# DSO_Control.net
KiCad netlist of a schematic drawn in Altium Designer
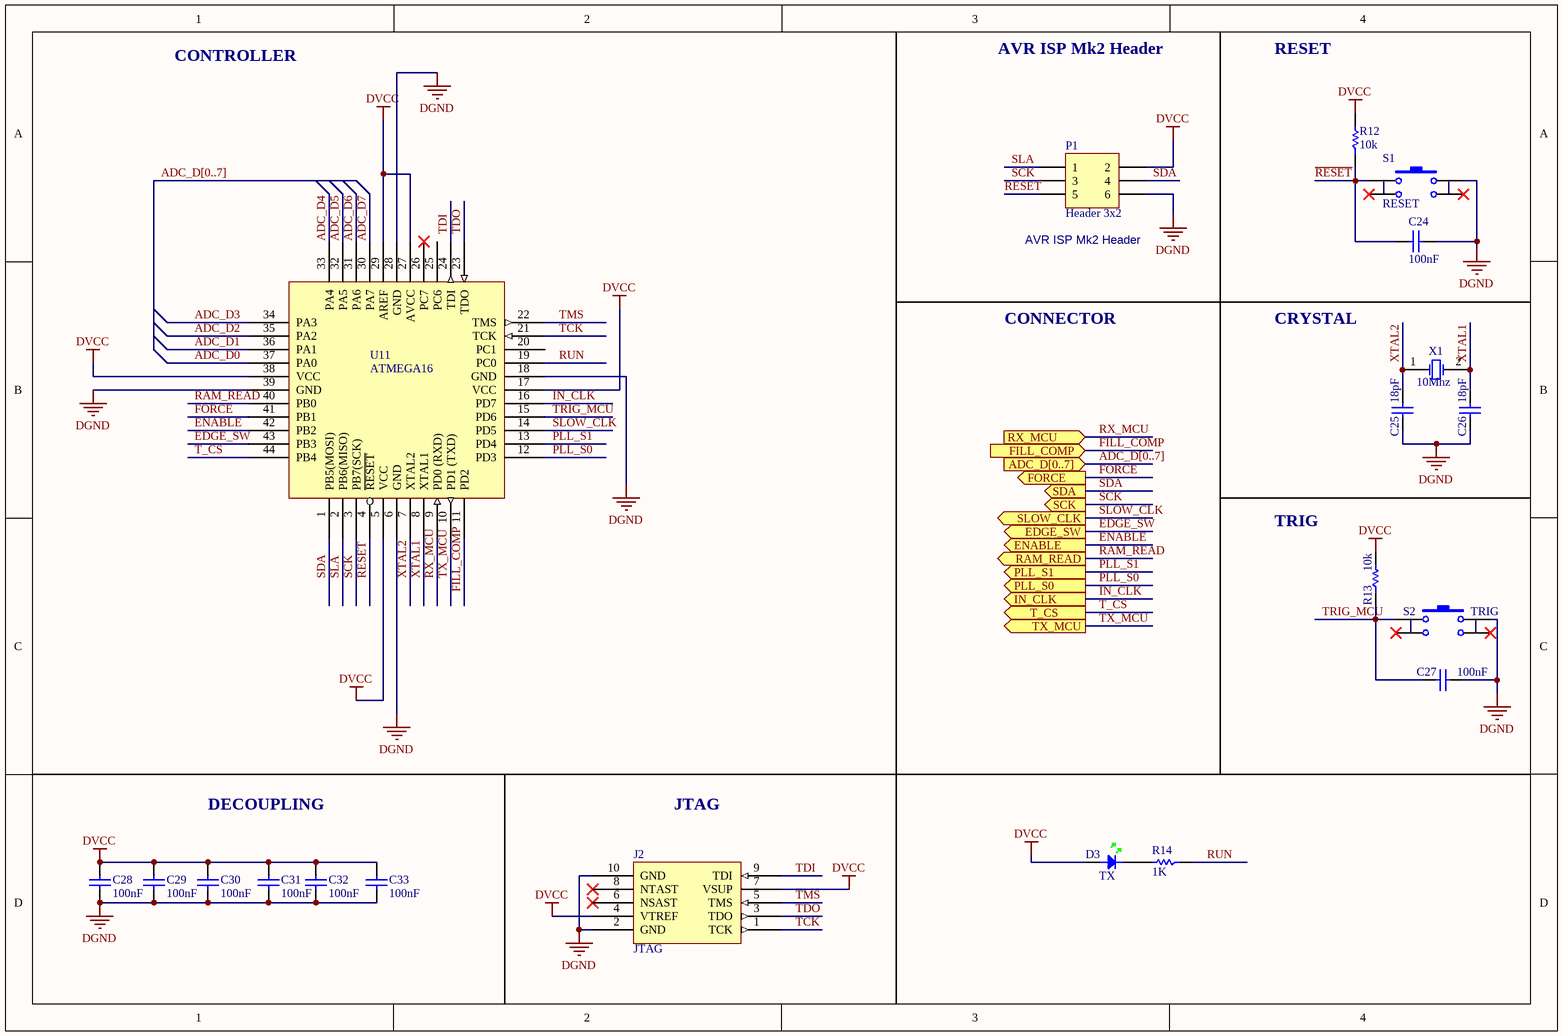
[diagram p0: DSO_Control.SchDoc]

(export (version "E")
  (design (tool "Eeschema 10.0.6"))
  (components
    (comp (ref "C24")
      (value "100nF")
      (footprint "0805C")
      (description "Capacitor")
      (fields (field (name "REVIEWED BY") "RM - 2018/08/05"))
      (libsource (lib "DSO") (part "C"))
    )
    (comp (ref "C25")
      (value "18pF")
      (footprint "0805C")
      (description "Capacitor")
      (fields (field (name "REVIEWED BY") "RM - 2018/08/05"))
      (libsource (lib "DSO") (part "C"))
    )
    (comp (ref "C26")
      (value "18pF")
      (footprint "0805C")
      (description "Capacitor")
      (fields (field (name "REVIEWED BY") "RM - 2018/08/05"))
      (libsource (lib "DSO") (part "C"))
    )
    (comp (ref "C27")
      (value "100nF")
      (footprint "0805C")
      (description "Capacitor")
      (fields (field (name "REVIEWED BY") "RM - 2018/08/05"))
      (libsource (lib "DSO") (part "C"))
    )
    (comp (ref "C28")
      (value "100nF")
      (footprint "0805C")
      (description "Capacitor")
      (fields (field (name "REVIEWED BY") "RM - 2018/08/05"))
      (libsource (lib "DSO") (part "C"))
    )
    (comp (ref "C29")
      (value "100nF")
      (footprint "0805C")
      (description "Capacitor")
      (fields (field (name "REVIEWED BY") "RM - 2018/08/05"))
      (libsource (lib "DSO") (part "C"))
    )
    (comp (ref "C30")
      (value "100nF")
      (footprint "0805C")
      (description "Capacitor")
      (fields (field (name "REVIEWED BY") "RM - 2018/08/05"))
      (libsource (lib "DSO") (part "C"))
    )
    (comp (ref "C31")
      (value "100nF")
      (footprint "0805C")
      (description "Capacitor")
      (fields (field (name "REVIEWED BY") "RM - 2018/08/05"))
      (libsource (lib "DSO") (part "C"))
    )
    (comp (ref "C32")
      (value "100nF")
      (footprint "0805C")
      (description "Capacitor")
      (fields (field (name "REVIEWED BY") "RM - 2018/08/05"))
      (libsource (lib "DSO") (part "C"))
    )
    (comp (ref "C33")
      (value "100nF")
      (footprint "0805C")
      (description "Capacitor")
      (fields (field (name "REVIEWED BY") "RM - 2018/08/05"))
      (libsource (lib "DSO") (part "C"))
    )
    (comp (ref "D3")
      (value "TX")
      (footprint "0805D-GREEN")
      (description "Light Emitting Diode")
      (fields (field (name "REVIEWED BY") "RM - 2018/08/05"))
      (libsource (lib "DSO") (part "LED GREEN"))
    )
    (comp (ref "J2")
      (value "JTAG")
      (footprint "BOXEDVERT10")
      (description "JTAG_CON")
      (fields (field (name "REVIEWED BY") "RM - 2018/08/05"))
      (libsource (lib "DSO") (part "JTAG_CON"))
    )
    (comp (ref "P1")
      (value "Header 3x2")
      (footprint "HDR3x2")
      (description "Header, 5-Pin")
      (fields (field (name "REVIEWED BY") "RM - 2018/08/05"))
      (libsource (lib "DSO") (part "Header 3x2"))
    )
    (comp (ref "R12")
      (value "10k")
      (footprint "0805")
      (description "Resistor")
      (fields (field (name "REVIEWED BY") "RM - 2018/08/05"))
      (libsource (lib "DSO") (part "R"))
    )
    (comp (ref "R13")
      (value "10k")
      (footprint "0805")
      (description "Resistor")
      (fields (field (name "REVIEWED BY") "RM - 2018/08/05"))
      (libsource (lib "DSO") (part "R"))
    )
    (comp (ref "R14")
      (value "1K")
      (footprint "0805")
      (description "Resistor")
      (libsource (lib "DSO") (part "R"))
    )
    (comp (ref "S1")
      (value "RESET")
      (footprint "SPST PB SWITCH SMD")
      (description "Momentary Push Button Switch 1P 1T 2pins")
      (fields (field (name "REVIEWED BY") "RM - 2018/08/05"))
      (libsource (lib "DSO") (part "SW_PB_1P1T4"))
    )
    (comp (ref "S2")
      (value "TRIG")
      (footprint "SPST PB SWITCH SMD")
      (description "Momentary Push Button Switch 1P 1T 2pins")
      (fields (field (name "REVIEWED BY") "RM - 2018/08/05"))
      (libsource (lib "DSO") (part "SW_PB_1P1T4"))
    )
    (comp (ref "U11")
      (value "ATMEGA16")
      (footprint "QFP-48")
      (description "ATMEGA16 Microcontroller")
      (fields (field (name "REVIEWED BY") "RM - 2018/08/05"))
      (libsource (lib "DSO") (part "ATMEGA16"))
    )
    (comp (ref "X1")
      (value "10Mhz")
      (footprint "XTAL_FLAT_SMD")
      (description "Crystal Oscillator")
      (fields (field (name "REVIEWED BY") "RM - 2018/08/05"))
      (libsource (lib "DSO") (part "XTAL"))
    )
  )
  (nets
    (net (code "1") (name "/ADC_D0") (class "Default")
      (node (ref "U11") (pin "37") (pinfunction "PA0_37") (pintype "passive"))
    )
    (net (code "2") (name "/ADC_D1") (class "Default")
      (node (ref "U11") (pin "36") (pinfunction "PA1_36") (pintype "passive"))
    )
    (net (code "3") (name "/ADC_D2") (class "Default")
      (node (ref "U11") (pin "35") (pinfunction "PA2_35") (pintype "passive"))
    )
    (net (code "4") (name "/ADC_D3") (class "Default")
      (node (ref "U11") (pin "34") (pinfunction "PA3_34") (pintype "passive"))
    )
    (net (code "5") (name "/ADC_D4") (class "Default")
      (node (ref "U11") (pin "33") (pinfunction "PA4_33") (pintype "passive"))
    )
    (net (code "6") (name "/ADC_D5") (class "Default")
      (node (ref "U11") (pin "32") (pinfunction "PA5_32") (pintype "passive"))
    )
    (net (code "7") (name "/ADC_D6") (class "Default")
      (node (ref "U11") (pin "31") (pinfunction "PA6_31") (pintype "passive"))
    )
    (net (code "8") (name "/ADC_D7") (class "Default")
      (node (ref "U11") (pin "30") (pinfunction "PA7_30") (pintype "passive"))
    )
    (net (code "10") (name "/EDGE_SW") (class "Default")
      (node (ref "U11") (pin "43") (pinfunction "PB3_43") (pintype "passive"))
    )
    (net (code "11") (name "/ENABLE") (class "Default")
      (node (ref "U11") (pin "42") (pinfunction "PB2_42") (pintype "passive"))
    )
    (net (code "12") (name "/FILL_COMP") (class "Default")
      (node (ref "U11") (pin "11") (pinfunction "PD2_11") (pintype "passive"))
    )
    (net (code "13") (name "/FORCE") (class "Default")
      (node (ref "U11") (pin "41") (pinfunction "PB1_41") (pintype "passive"))
    )
    (net (code "14") (name "/IN_CLK") (class "Default")
      (node (ref "U11") (pin "16") (pinfunction "PD7_16") (pintype "passive"))
    )
    (net (code "15") (name "/PLL_S0") (class "Default")
      (node (ref "U11") (pin "12") (pinfunction "PD3_12") (pintype "passive"))
    )
    (net (code "16") (name "/PLL_S1") (class "Default")
      (node (ref "U11") (pin "13") (pinfunction "PD4_13") (pintype "passive"))
    )
    (net (code "17") (name "/RAM_READ") (class "Default")
      (node (ref "U11") (pin "40") (pinfunction "PB0_40") (pintype "passive"))
    )
    (net (code "18") (name "/RUN") (class "Default")
      (node (ref "R14") (pin "1") (pintype "passive"))
      (node (ref "U11") (pin "19") (pinfunction "PC0_19") (pintype "passive"))
    )
    (net (code "19") (name "/RX_MCU") (class "Default")
      (node (ref "U11") (pin "9") (pinfunction "PD0_(RXD)_9") (pintype "input"))
    )
    (net (code "20") (name "/SCK") (class "Default")
      (node (ref "P1") (pin "3") (pinfunction "3_3") (pintype "passive"))
      (node (ref "U11") (pin "3") (pinfunction "PB7(SCK)_3") (pintype "passive"))
    )
    (net (code "21") (name "/SDA") (class "Default")
      (node (ref "P1") (pin "4") (pinfunction "4_4") (pintype "passive"))
      (node (ref "U11") (pin "1") (pinfunction "PB5(MOSI)_1") (pintype "passive"))
    )
    (net (code "22") (name "/SLA") (class "Default")
      (node (ref "P1") (pin "1") (pinfunction "1_1") (pintype "passive"))
      (node (ref "U11") (pin "2") (pinfunction "PB6(MISO)_2") (pintype "passive"))
    )
    (net (code "23") (name "/SLOW_CLK") (class "Default")
      (node (ref "U11") (pin "14") (pinfunction "PD5_14") (pintype "passive"))
    )
    (net (code "24") (name "/TCK") (class "Default")
      (node (ref "J2") (pin "1") (pinfunction "TCK_1") (pintype "output"))
      (node (ref "U11") (pin "21") (pinfunction "TCK_21") (pintype "input"))
    )
    (net (code "25") (name "/TDI") (class "Default")
      (node (ref "J2") (pin "9") (pinfunction "TDI_9") (pintype "input"))
      (node (ref "U11") (pin "24") (pinfunction "TDI_24") (pintype "output"))
    )
    (net (code "26") (name "/TDO") (class "Default")
      (node (ref "J2") (pin "3") (pinfunction "TDO_3") (pintype "output"))
      (node (ref "U11") (pin "23") (pinfunction "TDO_23") (pintype "input"))
    )
    (net (code "27") (name "/TMS") (class "Default")
      (node (ref "J2") (pin "5") (pinfunction "TMS_5") (pintype "input"))
      (node (ref "U11") (pin "22") (pinfunction "TMS_22") (pintype "output"))
    )
    (net (code "28") (name "/TRIG_MCU") (class "Default")
      (node (ref "C27") (pin "2") (pinfunction "2_2") (pintype "passive"))
      (node (ref "R13") (pin "1") (pintype "passive"))
      (node (ref "S2") (pin "1") (pinfunction "1_1") (pintype "passive"))
      (node (ref "U11") (pin "15") (pinfunction "PD6_15") (pintype "passive"))
    )
    (net (code "29") (name "/TX_MCU") (class "Default")
      (node (ref "U11") (pin "10") (pinfunction "PD1_(TXD)_10") (pintype "output"))
    )
    (net (code "30") (name "/T_CS") (class "Default")
      (node (ref "U11") (pin "44") (pinfunction "PB4_44") (pintype "passive"))
    )
    (net (code "31") (name "/XTAL1") (class "Default")
      (node (ref "C26") (pin "1") (pinfunction "1_1") (pintype "passive"))
      (node (ref "U11") (pin "8") (pinfunction "XTAL1_8") (pintype "passive"))
      (node (ref "X1") (pin "2") (pinfunction "OSC2_2") (pintype "passive"))
    )
    (net (code "32") (name "/XTAL2") (class "Default")
      (node (ref "C25") (pin "1") (pinfunction "1_1") (pintype "passive"))
      (node (ref "U11") (pin "7") (pinfunction "XTAL2_7") (pintype "passive"))
      (node (ref "X1") (pin "1") (pinfunction "OSC1_1") (pintype "passive"))
    )
    (net (code "33") (name "/~{RESET}") (class "Default")
      (node (ref "C24") (pin "2") (pinfunction "2_2") (pintype "passive"))
      (node (ref "P1") (pin "5") (pinfunction "5_5") (pintype "passive"))
      (node (ref "R12") (pin "1") (pintype "passive"))
      (node (ref "S1") (pin "1") (pinfunction "1_1") (pintype "passive"))
      (node (ref "U11") (pin "4") (pinfunction "~{RESET}_4") (pintype "passive"))
    )
    (net (code "34") (name "DGND") (class "Default")
      (node (ref "C24") (pin "1") (pinfunction "1_1") (pintype "passive"))
      (node (ref "C25") (pin "2") (pinfunction "2_2") (pintype "passive"))
      (node (ref "C26") (pin "2") (pinfunction "2_2") (pintype "passive"))
      (node (ref "C27") (pin "1") (pinfunction "1_1") (pintype "passive"))
      (node (ref "C28") (pin "2") (pinfunction "2_2") (pintype "passive"))
      (node (ref "C29") (pin "2") (pinfunction "2_2") (pintype "passive"))
      (node (ref "C30") (pin "2") (pinfunction "2_2") (pintype "passive"))
      (node (ref "C31") (pin "2") (pinfunction "2_2") (pintype "passive"))
      (node (ref "C32") (pin "2") (pinfunction "2_2") (pintype "passive"))
      (node (ref "C33") (pin "2") (pinfunction "2_2") (pintype "passive"))
      (node (ref "J2") (pin "10") (pinfunction "GND_10") (pintype "passive"))
      (node (ref "J2") (pin "2") (pinfunction "GND_2") (pintype "passive"))
      (node (ref "P1") (pin "6") (pinfunction "6_6") (pintype "passive"))
      (node (ref "S1") (pin "2") (pinfunction "2_2") (pintype "passive"))
      (node (ref "S2") (pin "2") (pinfunction "2_2") (pintype "passive"))
      (node (ref "U11") (pin "18") (pinfunction "GND_18") (pintype "passive"))
      (node (ref "U11") (pin "28") (pinfunction "GND_28") (pintype "passive"))
      (node (ref "U11") (pin "39") (pinfunction "GND_39") (pintype "passive"))
      (node (ref "U11") (pin "6") (pinfunction "GND_6") (pintype "passive"))
    )
    (net (code "35") (name "DVCC") (class "Default")
      (node (ref "C28") (pin "1") (pinfunction "1_1") (pintype "passive"))
      (node (ref "C29") (pin "1") (pinfunction "1_1") (pintype "passive"))
      (node (ref "C30") (pin "1") (pinfunction "1_1") (pintype "passive"))
      (node (ref "C31") (pin "1") (pinfunction "1_1") (pintype "passive"))
      (node (ref "C32") (pin "1") (pinfunction "1_1") (pintype "passive"))
      (node (ref "C33") (pin "1") (pinfunction "1_1") (pintype "passive"))
      (node (ref "D3") (pin "A") (pinfunction "A_A") (pintype "passive"))
      (node (ref "J2") (pin "4") (pinfunction "VTREF_4") (pintype "power_in"))
      (node (ref "J2") (pin "7") (pinfunction "VSUP_7") (pintype "passive"))
      (node (ref "P1") (pin "2") (pinfunction "2_2") (pintype "passive"))
      (node (ref "R12") (pin "2") (pintype "passive"))
      (node (ref "R13") (pin "2") (pintype "passive"))
      (node (ref "U11") (pin "17") (pinfunction "VCC_17") (pintype "passive"))
      (node (ref "U11") (pin "27") (pinfunction "AVCC_27") (pintype "passive"))
      (node (ref "U11") (pin "29") (pinfunction "AREF_29") (pintype "passive"))
      (node (ref "U11") (pin "38") (pinfunction "VCC_38") (pintype "passive"))
      (node (ref "U11") (pin "5") (pinfunction "VCC_5") (pintype "passive"))
    )
    (net (code "36") (name "Net-(D3-PadK)") (class "Default")
      (node (ref "D3") (pin "K") (pinfunction "K_K") (pintype "passive"))
      (node (ref "R14") (pin "2") (pintype "passive"))
    )
    (net (code "37") (name "unconnected-(J2-NSAST-Pad6)") (class "Default")
      (node (ref "J2") (pin "6") (pinfunction "NSAST_6") (pintype "passive+no_connect"))
    )
    (net (code "38") (name "unconnected-(J2-NTAST-Pad8)") (class "Default")
      (node (ref "J2") (pin "8") (pinfunction "NTAST_8") (pintype "passive+no_connect"))
    )
    (net (code "39") (name "unconnected-(S1-Pad3)") (class "Default")
      (node (ref "S1") (pin "3") (pinfunction "3_3") (pintype "passive+no_connect"))
    )
    (net (code "40") (name "unconnected-(S1-Pad4)") (class "Default")
      (node (ref "S1") (pin "4") (pinfunction "4_4") (pintype "passive+no_connect"))
    )
    (net (code "41") (name "unconnected-(S2-Pad3)") (class "Default")
      (node (ref "S2") (pin "3") (pinfunction "3_3") (pintype "passive+no_connect"))
    )
    (net (code "42") (name "unconnected-(S2-Pad4)") (class "Default")
      (node (ref "S2") (pin "4") (pinfunction "4_4") (pintype "passive+no_connect"))
    )
    (net (code "43") (name "unconnected-(U11-PC1-Pad20)") (class "Default")
      (node (ref "U11") (pin "20") (pinfunction "PC1_20") (pintype "passive"))
    )
    (net (code "44") (name "unconnected-(U11-PC6-Pad25)") (class "Default")
      (node (ref "U11") (pin "25") (pinfunction "PC6_25") (pintype "passive"))
    )
    (net (code "45") (name "unconnected-(U11-PC7-Pad26)") (class "Default")
      (node (ref "U11") (pin "26") (pinfunction "PC7_26") (pintype "passive+no_connect"))
    )
  )
)
